# Sensor.net
KiCad netlist of a schematic drawn in Altium Designer
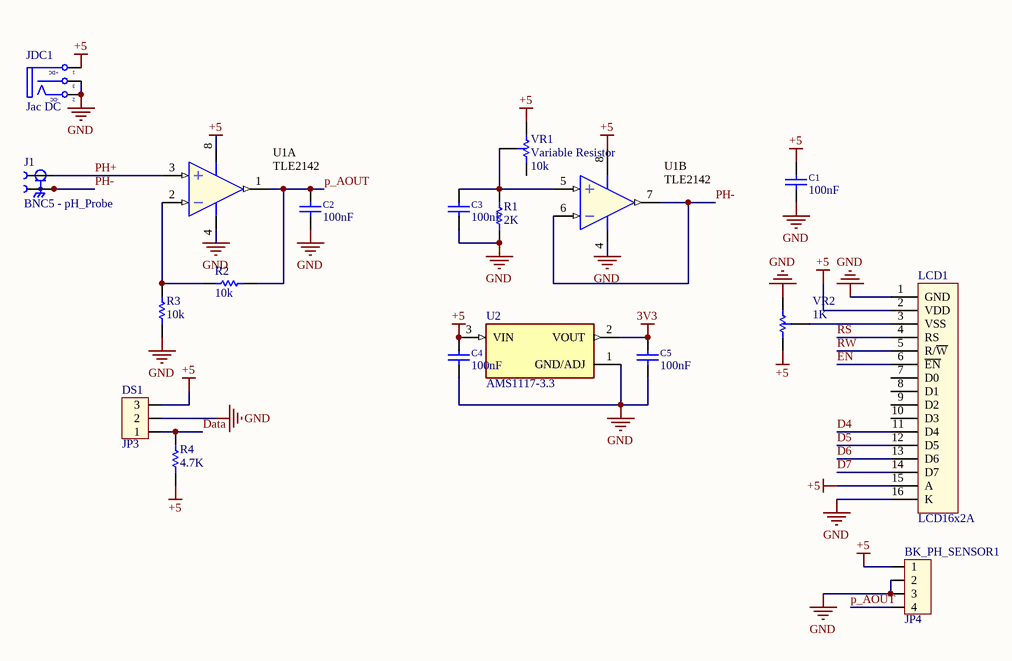
[diagram p0: Sensor.SchDoc]

(export (version "E")
  (design (tool "Eeschema 10.0.6"))
  (components
    (comp (ref "BK_PH_SENSOR1")
      (value "JP4")
      (footprint "CON4")
      (description "Connector 4")
      (libsource (lib "Kiet") (part "Con4"))
    )
    (comp (ref "C1")
      (value "100nF")
      (footprint "C2012-0805")
      (description "Capacitor")
      (fields (field (name "PUBLISHER") "Hoang Nguyen"))
      (libsource (lib "Kiet") (part "Capacitor"))
    )
    (comp (ref "C2")
      (value "100nF")
      (footprint "C2012-0805")
      (description "Capacitor")
      (fields (field (name "PUBLISHER") "Hoang Nguyen"))
      (libsource (lib "Kiet") (part "Capacitor"))
    )
    (comp (ref "C3")
      (value "100nF")
      (footprint "C2012-0805")
      (description "Capacitor")
      (fields (field (name "PUBLISHER") "Hoang Nguyen"))
      (libsource (lib "Kiet") (part "Capacitor"))
    )
    (comp (ref "C4")
      (value "100nF")
      (footprint "C2012-0805")
      (description "Capacitor")
      (fields (field (name "PUBLISHER") "Hoang Nguyen"))
      (libsource (lib "Kiet") (part "Capacitor"))
    )
    (comp (ref "C5")
      (value "100nF")
      (footprint "C2012-0805")
      (description "Capacitor")
      (fields (field (name "PUBLISHER") "Hoang Nguyen"))
      (libsource (lib "Kiet") (part "Capacitor"))
    )
    (comp (ref "DS1")
      (value "JP3")
      (footprint "CON3")
      (description "Connector 3")
      (libsource (lib "Kiet") (part "Con3"))
    )
    (comp (ref "J1")
      (value "BNC5 - pH_Probe")
      (footprint "SAMTEC_BNC5-J-P-GN-RA-BH2D")
      (description "BNC Connector Jack, Female Socket 50Ohm Panel Mount, Through Hole, Right Angle Solder")
      (fields (field (name "MP") "BNC5-J-P-GN-RA-BH2D") (field (name "MF") "Samtec"))
      (libsource (lib "BNC5-J-P-GN-RA-BH2D") (part "BNC5-J-P-GN-RA-BH2D"))
    )
    (comp (ref "JDC1")
      (value "Jac DC")
      (footprint "DC-IN")
      (description "Jac DC input")
      (libsource (lib "Kiet") (part "DCIN"))
    )
    (comp (ref "LCD1")
      (value "LCD16x2A")
      (footprint "LCD16X2")
      (description "LCD dipslay 16 char, 2 line")
      (libsource (lib "Kiet") (part "LCD16x2"))
    )
    (comp (ref "R1")
      (value "2K")
      (footprint "R-0805")
      (description "Resistor")
      (fields (field (name "Comment") "RESISTOR") (field (name "PUBLISHER") "Altium Limited"))
      (libsource (lib "Kiet") (part "RESISTOR"))
    )
    (comp (ref "R2")
      (value "10k")
      (footprint "R-0805")
      (description "Resistor")
      (fields (field (name "Comment") "RESISTOR") (field (name "PUBLISHER") "Altium Limited"))
      (libsource (lib "Kiet") (part "RESISTOR"))
    )
    (comp (ref "R3")
      (value "10k")
      (footprint "R-0805")
      (description "Resistor")
      (fields (field (name "Comment") "RESISTOR") (field (name "PUBLISHER") "Altium Limited"))
      (libsource (lib "Kiet") (part "RESISTOR"))
    )
    (comp (ref "R4")
      (value "4.7K")
      (footprint "R-0805")
      (description "Resistor")
      (fields (field (name "Comment") "RESISTOR") (field (name "PUBLISHER") "Altium Limited"))
      (libsource (lib "Kiet") (part "RESISTOR"))
    )
    (comp (ref "U1")
      (value "TLE2142")
      (footprint "SOIC8")
      (description "Low-Power Dual Operational Amplifier")
      (fields (field (name "PUBLISHER") "Altium Limited"))
      (libsource (lib "Kiet") (part "LM2904"))
    )
    (comp (ref "U2")
      (value "AMS1117-3.3")
      (footprint "SOT229P700X180-4N")
      (description "Sot223/Pkg 1-Amp 3.3-Volt Low Drop Out Voltage Regulatator")
      (fields (field (name "MF") "Advanced Monolithic Systems"))
      (libsource (lib "AMS1117-3.3") (part "AMS1117-3.3"))
    )
    (comp (ref "VR1")
      (value "Variable Resistor")
      (footprint "VRes-R")
      (fields (field (name "ALTIUM_VALUE") "10k") (field (name "PUBLISHER") "Altium Limited"))
      (libsource (lib "Kiet") (part "Variable Resistor"))
    )
    (comp (ref "VR2")
      (value "1K")
      (footprint "VRes-C")
      (description "Variable Resistor")
      (fields (field (name "PUBLISHER") "Altium Limited"))
      (libsource (lib "Kiet") (part "Variable Resistor"))
    )
  )
  (nets
    (net (code "1") (name "+5") (class "Default")
      (node (ref "BK_PH_SENSOR1") (pin "1") (pinfunction "1_1") (pintype "passive"))
      (node (ref "C1") (pin "2") (pinfunction "2_2") (pintype "passive"))
      (node (ref "C4") (pin "2") (pinfunction "2_2") (pintype "passive"))
      (node (ref "DS1") (pin "3") (pinfunction "3_3") (pintype "passive"))
      (node (ref "JDC1") (pin "1") (pinfunction "T_1") (pintype "passive"))
      (node (ref "LCD1") (pin "15") (pinfunction "A_15") (pintype "passive"))
      (node (ref "LCD1") (pin "2") (pinfunction "VDD_2") (pintype "passive"))
      (node (ref "R4") (pin "1") (pinfunction "1_1") (pintype "passive"))
      (node (ref "U1") (pin "8") (pinfunction "V+_8") (pintype "power_in"))
      (node (ref "U2") (pin "3") (pinfunction "VIN_3") (pintype "input"))
      (node (ref "VR1") (pin "1") (pinfunction "1_1") (pintype "passive"))
      (node (ref "VR2") (pin "1") (pinfunction "1_1") (pintype "passive"))
    )
    (net (code "2") (name "/D4") (class "Default")
      (node (ref "LCD1") (pin "11") (pinfunction "D4_11") (pintype "passive"))
    )
    (net (code "3") (name "/D5") (class "Default")
      (node (ref "LCD1") (pin "12") (pinfunction "D5_12") (pintype "passive"))
    )
    (net (code "4") (name "/D6") (class "Default")
      (node (ref "LCD1") (pin "13") (pinfunction "D6_13") (pintype "passive"))
    )
    (net (code "5") (name "/D7") (class "Default")
      (node (ref "LCD1") (pin "14") (pinfunction "D7_14") (pintype "passive"))
    )
    (net (code "6") (name "/Data") (class "Default")
      (node (ref "DS1") (pin "1") (pinfunction "1_1") (pintype "passive"))
      (node (ref "R4") (pin "2") (pinfunction "2_2") (pintype "passive"))
    )
    (net (code "7") (name "/EN") (class "Default")
      (node (ref "LCD1") (pin "6") (pinfunction "~{EN}_6") (pintype "passive"))
    )
    (net (code "8") (name "/PH+") (class "Default")
      (node (ref "J1") (pin "1") (pinfunction "1_1") (pintype "passive"))
      (node (ref "U1") (pin "3") (pinfunction "IN+_3") (pintype "input"))
    )
    (net (code "9") (name "/PH-") (class "Default")
      (node (ref "J1") (pin "S_1") (pinfunction "2_S_1") (pintype "passive"))
      (node (ref "J1") (pin "S_2") (pinfunction "2_S_2") (pintype "passive"))
      (node (ref "J1") (pin "S_3") (pinfunction "2_S_3") (pintype "passive"))
      (node (ref "J1") (pin "S_4") (pinfunction "2_S_4") (pintype "passive"))
      (node (ref "U1") (pin "6") (pinfunction "IN-_6") (pintype "input"))
      (node (ref "U1") (pin "7") (pinfunction "OUT_7") (pintype "output"))
    )
    (net (code "10") (name "/RS") (class "Default")
      (node (ref "LCD1") (pin "4") (pinfunction "RS_4") (pintype "passive"))
    )
    (net (code "11") (name "/RW") (class "Default")
      (node (ref "LCD1") (pin "5") (pinfunction "R/~{W}_5") (pintype "passive"))
    )
    (net (code "12") (name "/p_AOUT") (class "Default")
      (node (ref "BK_PH_SENSOR1") (pin "4") (pinfunction "4_4") (pintype "passive"))
      (node (ref "C2") (pin "2") (pinfunction "2_2") (pintype "passive"))
      (node (ref "R2") (pin "2") (pinfunction "2_2") (pintype "passive"))
      (node (ref "U1") (pin "1") (pinfunction "OUT_1") (pintype "output"))
    )
    (net (code "13") (name "3V3") (class "Default")
      (node (ref "C5") (pin "2") (pinfunction "2_2") (pintype "passive"))
      (node (ref "U2") (pin "2") (pinfunction "VOUT_2") (pintype "output"))
    )
    (net (code "14") (name "GND") (class "Default")
      (node (ref "BK_PH_SENSOR1") (pin "2") (pinfunction "2_2") (pintype "passive"))
      (node (ref "BK_PH_SENSOR1") (pin "3") (pinfunction "3_3") (pintype "passive"))
      (node (ref "C1") (pin "1") (pinfunction "1_1") (pintype "passive"))
      (node (ref "C2") (pin "1") (pinfunction "1_1") (pintype "passive"))
      (node (ref "C3") (pin "1") (pinfunction "1_1") (pintype "passive"))
      (node (ref "C4") (pin "1") (pinfunction "1_1") (pintype "passive"))
      (node (ref "C5") (pin "1") (pinfunction "1_1") (pintype "passive"))
      (node (ref "DS1") (pin "2") (pinfunction "2_2") (pintype "passive"))
      (node (ref "JDC1") (pin "2") (pinfunction "TN_2") (pintype "passive"))
      (node (ref "JDC1") (pin "3") (pinfunction "S_3") (pintype "power_in"))
      (node (ref "LCD1") (pin "1") (pinfunction "GND_1") (pintype "passive"))
      (node (ref "LCD1") (pin "16") (pinfunction "K_16") (pintype "passive"))
      (node (ref "R1") (pin "1") (pinfunction "1_1") (pintype "passive"))
      (node (ref "R3") (pin "1") (pinfunction "1_1") (pintype "passive"))
      (node (ref "U1") (pin "4") (pinfunction "GND_4") (pintype "power_in"))
      (node (ref "U2") (pin "1") (pinfunction "GND/ADJ_1") (pintype "power_in"))
      (node (ref "VR2") (pin "3") (pinfunction "3_3") (pintype "passive"))
    )
    (net (code "15") (name "Net-(LCD1-VSS)") (class "Default")
      (node (ref "LCD1") (pin "3") (pinfunction "VSS_3") (pintype "passive"))
      (node (ref "VR2") (pin "2") (pinfunction "2_2") (pintype "passive"))
    )
    (net (code "16") (name "Net-(U1A-IN-)") (class "Default")
      (node (ref "R2") (pin "1") (pinfunction "1_1") (pintype "passive"))
      (node (ref "R3") (pin "2") (pinfunction "2_2") (pintype "passive"))
      (node (ref "U1") (pin "2") (pinfunction "IN-_2") (pintype "input"))
    )
    (net (code "17") (name "Net-(U1B-IN+)") (class "Default")
      (node (ref "C3") (pin "2") (pinfunction "2_2") (pintype "passive"))
      (node (ref "R1") (pin "2") (pinfunction "2_2") (pintype "passive"))
      (node (ref "U1") (pin "5") (pinfunction "IN+_5") (pintype "input"))
      (node (ref "VR1") (pin "2") (pinfunction "2_2") (pintype "passive"))
    )
    (net (code "18") (name "unconnected-(LCD1-D0-Pad7)") (class "Default")
      (node (ref "LCD1") (pin "7") (pinfunction "D0_7") (pintype "passive"))
    )
    (net (code "19") (name "unconnected-(LCD1-D1-Pad8)") (class "Default")
      (node (ref "LCD1") (pin "8") (pinfunction "D1_8") (pintype "passive"))
    )
    (net (code "20") (name "unconnected-(LCD1-D2-Pad9)") (class "Default")
      (node (ref "LCD1") (pin "9") (pinfunction "D2_9") (pintype "passive"))
    )
    (net (code "21") (name "unconnected-(LCD1-D3-Pad10)") (class "Default")
      (node (ref "LCD1") (pin "10") (pinfunction "D3_10") (pintype "passive"))
    )
    (net (code "22") (name "unconnected-(VR1-Pad3)") (class "Default")
      (node (ref "VR1") (pin "3") (pinfunction "3_3") (pintype "passive"))
    )
  )
)
